# amplifier.net
KiCad netlist of a schematic drawn in EAGLE
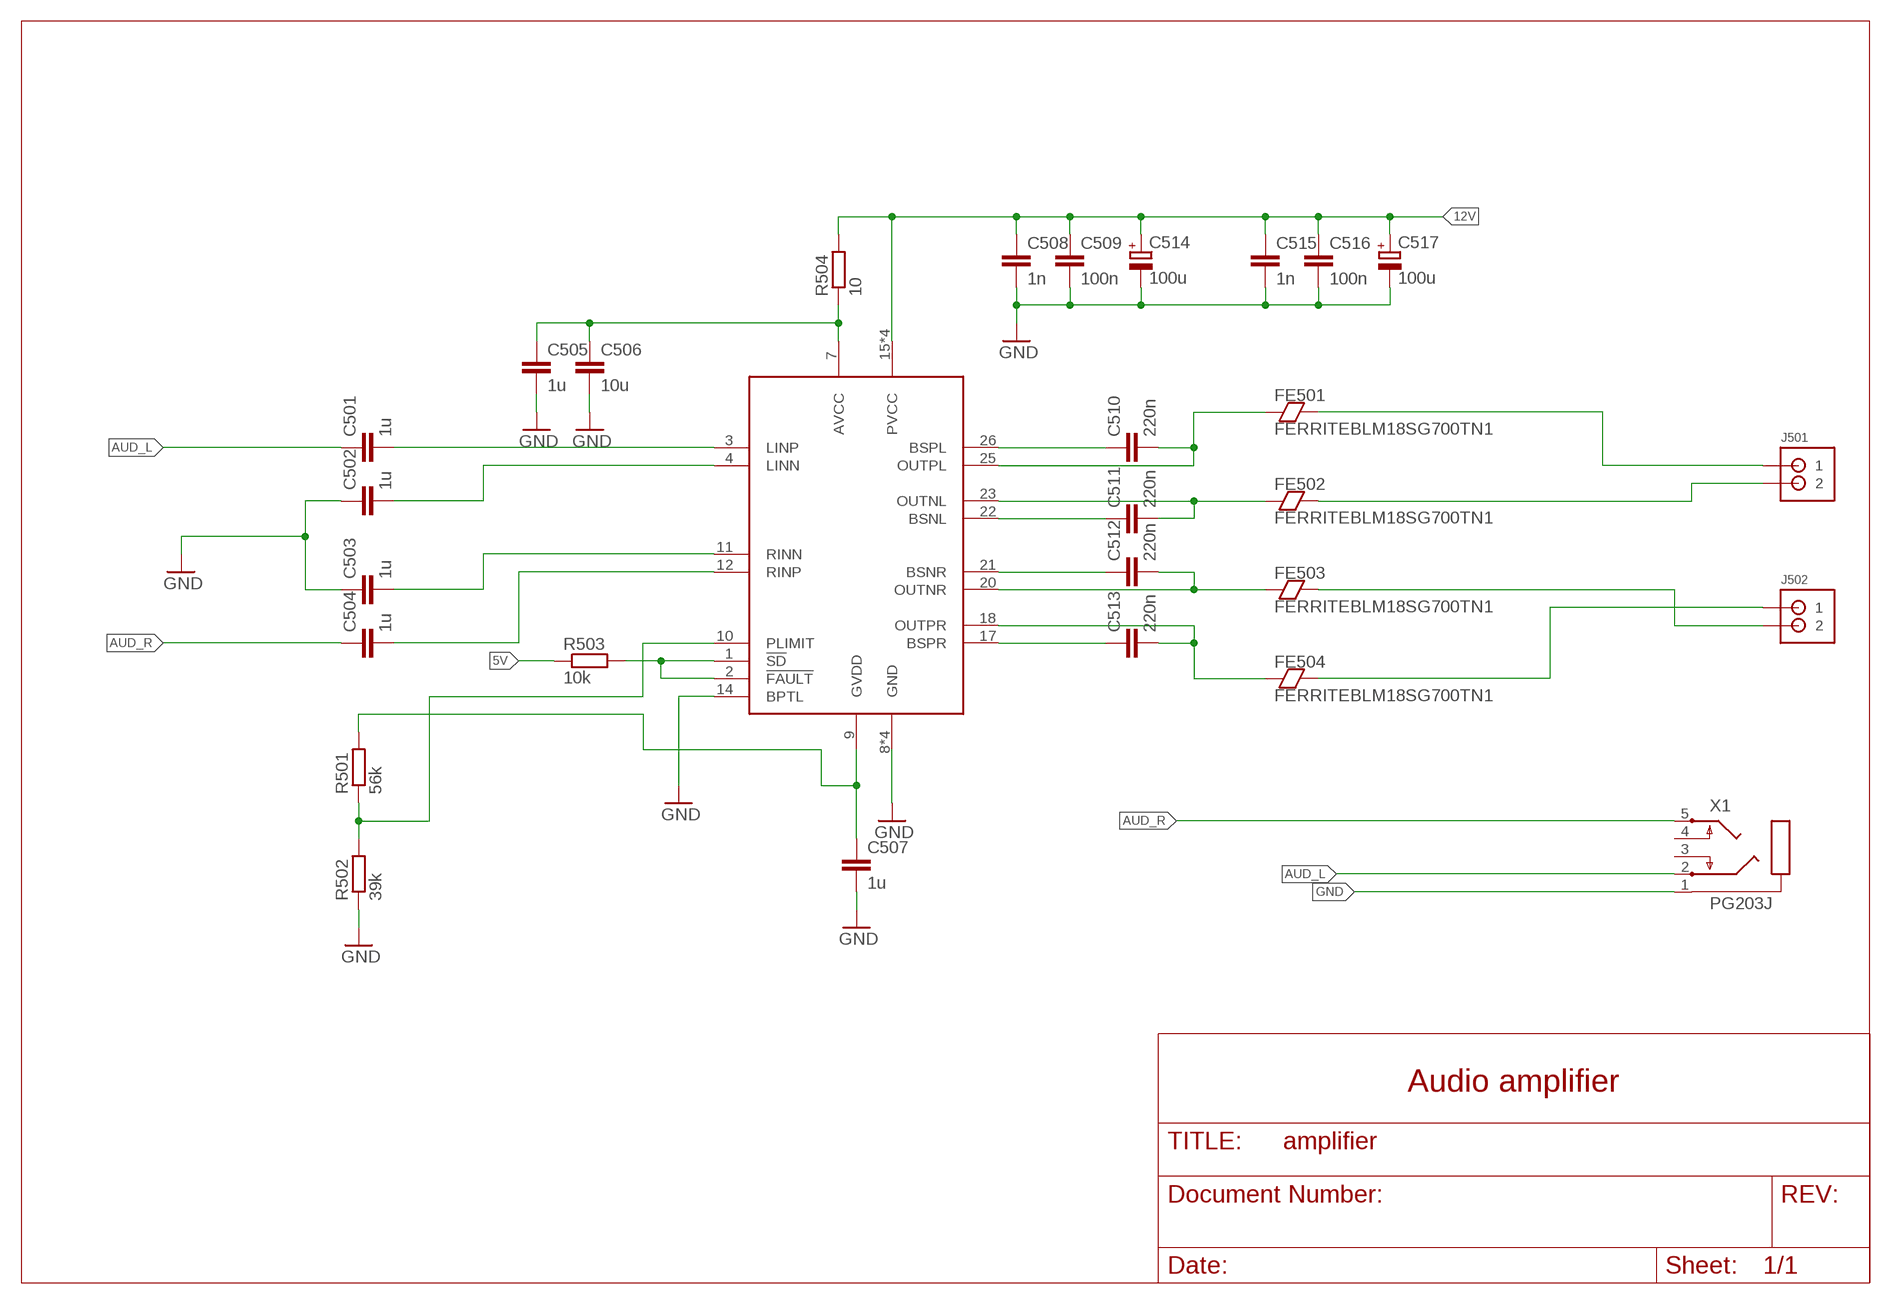
[diagram p0: schematic, sheet 1]

(export (version "E")
  (design (tool "Eeschema 10.0.6"))
  (components
    (comp (ref "C501")
      (value "1u")
      (footprint "eagle-import:C0603")
      (libsource (lib "eagle-import") (part "C0603"))
    )
    (comp (ref "C502")
      (value "1u")
      (footprint "eagle-import:C0603")
      (libsource (lib "eagle-import") (part "C0603"))
    )
    (comp (ref "C503")
      (value "1u")
      (footprint "eagle-import:C0603")
      (libsource (lib "eagle-import") (part "C0603"))
    )
    (comp (ref "C504")
      (value "1u")
      (footprint "eagle-import:C0603")
      (libsource (lib "eagle-import") (part "C0603"))
    )
    (comp (ref "C505")
      (value "1u")
      (footprint "eagle-import:C0603")
      (libsource (lib "eagle-import") (part "C0603"))
    )
    (comp (ref "C506")
      (value "10u")
      (footprint "eagle-import:C0603")
      (libsource (lib "eagle-import") (part "C0603"))
    )
    (comp (ref "C507")
      (value "1u")
      (footprint "eagle-import:C0603")
      (libsource (lib "eagle-import") (part "C0603"))
    )
    (comp (ref "C508")
      (value "1n")
      (footprint "eagle-import:C0603")
      (libsource (lib "eagle-import") (part "C0603"))
    )
    (comp (ref "C509")
      (value "100n")
      (footprint "eagle-import:C0603")
      (libsource (lib "eagle-import") (part "C0603"))
    )
    (comp (ref "C510")
      (value "220n")
      (footprint "eagle-import:C0603")
      (libsource (lib "eagle-import") (part "C0603"))
    )
    (comp (ref "C511")
      (value "220n")
      (footprint "eagle-import:C0603")
      (libsource (lib "eagle-import") (part "C0603"))
    )
    (comp (ref "C512")
      (value "220n")
      (footprint "eagle-import:C0603")
      (libsource (lib "eagle-import") (part "C0603"))
    )
    (comp (ref "C513")
      (value "220n")
      (footprint "eagle-import:C0603")
      (libsource (lib "eagle-import") (part "C0603"))
    )
    (comp (ref "C514")
      (value "100u")
      (footprint "eagle-import:CAP6.6X8")
      (libsource (lib "eagle-import") (part "C_POL6.6"))
    )
    (comp (ref "C515")
      (value "1n")
      (footprint "eagle-import:C0603")
      (libsource (lib "eagle-import") (part "C0603"))
    )
    (comp (ref "C516")
      (value "100n")
      (footprint "eagle-import:C0603")
      (libsource (lib "eagle-import") (part "C0603"))
    )
    (comp (ref "C517")
      (value "100u")
      (footprint "eagle-import:CAP6.6X8")
      (libsource (lib "eagle-import") (part "C_POL6.6"))
    )
    (comp (ref "FE501")
      (value "FERRITEBLM18SG700TN1")
      (footprint "eagle-import:R0603")
      (fields (field (name "MPN") "BLM18SG700TN1D"))
      (libsource (lib "eagle-import") (part "FERRITEBLM18SG700TN1"))
    )
    (comp (ref "FE502")
      (value "FERRITEBLM18SG700TN1")
      (footprint "eagle-import:R0603")
      (fields (field (name "MPN") "BLM18SG700TN1D"))
      (libsource (lib "eagle-import") (part "FERRITEBLM18SG700TN1"))
    )
    (comp (ref "FE503")
      (value "FERRITEBLM18SG700TN1")
      (footprint "eagle-import:R0603")
      (fields (field (name "MPN") "BLM18SG700TN1D"))
      (libsource (lib "eagle-import") (part "FERRITEBLM18SG700TN1"))
    )
    (comp (ref "FE504")
      (value "FERRITEBLM18SG700TN1")
      (footprint "eagle-import:R0603")
      (fields (field (name "MPN") "BLM18SG700TN1D"))
      (libsource (lib "eagle-import") (part "FERRITEBLM18SG700TN1"))
    )
    (comp (ref "J501")
      (value "CONNECTOR-2JST-XH-2")
      (footprint "eagle-import:JST-XH-2")
      (fields (field (name "MPN") "B2B-XH-A (LF)(SN)"))
      (libsource (lib "eagle-import") (part "CONNECTOR-2JST-XH-2"))
    )
    (comp (ref "J502")
      (value "CONNECTOR-2JST-XH-2")
      (footprint "eagle-import:JST-XH-2")
      (fields (field (name "MPN") "B2B-XH-A (LF)(SN)"))
      (libsource (lib "eagle-import") (part "CONNECTOR-2JST-XH-2"))
    )
    (comp (ref "R501")
      (value "56k")
      (footprint "eagle-import:R0603")
      (libsource (lib "eagle-import") (part "R0603"))
    )
    (comp (ref "R502")
      (value "39k")
      (footprint "eagle-import:R0603")
      (libsource (lib "eagle-import") (part "R0603"))
    )
    (comp (ref "R503")
      (value "10k")
      (footprint "eagle-import:R0603")
      (libsource (lib "eagle-import") (part "R0603"))
    )
    (comp (ref "R504")
      (value "10")
      (footprint "eagle-import:R0603")
      (libsource (lib "eagle-import") (part "R0603"))
    )
    (comp (ref "U501")
      (value "TPA3136D2")
      (footprint "eagle-import:R-PDSO-G28")
      (libsource (lib "eagle-import") (part "TPA3136D2"))
    )
    (comp (ref "X1")
      (value "PG203J")
      (footprint "eagle-import:PG203J")
      (libsource (lib "eagle-import") (part "PG203J"))
    )
  )
  (nets
    (net (code "1") (name "5V") (class "Default")
      (node (ref "R503") (pin "1") (pinfunction "1_1") (pintype "passive"))
    )
    (net (code "2") (name "12V") (class "Default")
      (node (ref "C508") (pin "1") (pinfunction "1_1") (pintype "passive"))
      (node (ref "C509") (pin "1") (pinfunction "1_1") (pintype "passive"))
      (node (ref "C514") (pin "1") (pinfunction "+_1") (pintype "passive"))
      (node (ref "C515") (pin "1") (pinfunction "1_1") (pintype "passive"))
      (node (ref "C516") (pin "1") (pinfunction "1_1") (pintype "passive"))
      (node (ref "C517") (pin "1") (pinfunction "+_1") (pintype "passive"))
      (node (ref "R504") (pin "2") (pinfunction "2_2") (pintype "passive"))
      (node (ref "U501") (pin "15") (pinfunction "PVCC_15") (pintype "power_in"))
      (node (ref "U501") (pin "16") (pinfunction "PVCC_16") (pintype "power_in"))
      (node (ref "U501") (pin "27") (pinfunction "PVCC_27") (pintype "power_in"))
      (node (ref "U501") (pin "28") (pinfunction "PVCC_28") (pintype "power_in"))
    )
    (net (code "3") (name "AUD_L") (class "Default")
      (node (ref "C501") (pin "1") (pinfunction "1_1") (pintype "passive"))
      (node (ref "X1") (pin "2") (pinfunction "2_2") (pintype "passive"))
    )
    (net (code "4") (name "AUD_R") (class "Default")
      (node (ref "C504") (pin "1") (pinfunction "1_1") (pintype "passive"))
      (node (ref "X1") (pin "5") (pinfunction "5_5") (pintype "passive"))
    )
    (net (code "5") (name "GND") (class "Default")
      (node (ref "C502") (pin "1") (pinfunction "1_1") (pintype "passive"))
      (node (ref "C503") (pin "1") (pinfunction "1_1") (pintype "passive"))
      (node (ref "C505") (pin "2") (pinfunction "2_2") (pintype "passive"))
      (node (ref "C506") (pin "2") (pinfunction "2_2") (pintype "passive"))
      (node (ref "C507") (pin "2") (pinfunction "2_2") (pintype "passive"))
      (node (ref "C508") (pin "2") (pinfunction "2_2") (pintype "passive"))
      (node (ref "C509") (pin "2") (pinfunction "2_2") (pintype "passive"))
      (node (ref "C514") (pin "2") (pinfunction "-_2") (pintype "passive"))
      (node (ref "C515") (pin "2") (pinfunction "2_2") (pintype "passive"))
      (node (ref "C516") (pin "2") (pinfunction "2_2") (pintype "passive"))
      (node (ref "C517") (pin "2") (pinfunction "-_2") (pintype "passive"))
      (node (ref "R502") (pin "1") (pinfunction "1_1") (pintype "passive"))
      (node (ref "U501") (pin "14") (pinfunction "BPTL_14") (pintype "input"))
      (node (ref "U501") (pin "19") (pinfunction "GND_19") (pintype "power_in"))
      (node (ref "U501") (pin "24") (pinfunction "GND_24") (pintype "power_in"))
      (node (ref "U501") (pin "8") (pinfunction "GND_8") (pintype "power_in"))
      (node (ref "U501") (pin "POWER") (pinfunction "GND_POWER") (pintype "power_in"))
      (node (ref "X1") (pin "1") (pinfunction "1_1") (pintype "passive"))
    )
    (net (code "6") (name "Net-(J501-1)") (class "Default")
      (node (ref "FE501") (pin "2") (pinfunction "2_2") (pintype "passive"))
      (node (ref "J501") (pin "P1") (pinfunction "1_P1") (pintype "bidirectional"))
    )
    (net (code "7") (name "Net-(J501-2)") (class "Default")
      (node (ref "FE502") (pin "2") (pinfunction "2_2") (pintype "passive"))
      (node (ref "J501") (pin "P2") (pinfunction "2_P2") (pintype "bidirectional"))
    )
    (net (code "8") (name "Net-(J502-1)") (class "Default")
      (node (ref "FE504") (pin "2") (pinfunction "2_2") (pintype "passive"))
      (node (ref "J502") (pin "P1") (pinfunction "1_P1") (pintype "bidirectional"))
    )
    (net (code "9") (name "Net-(J502-2)") (class "Default")
      (node (ref "FE503") (pin "2") (pinfunction "2_2") (pintype "passive"))
      (node (ref "J502") (pin "P2") (pinfunction "2_P2") (pintype "bidirectional"))
    )
    (net (code "10") (name "Net-(U501-AVCC)") (class "Default")
      (node (ref "C505") (pin "1") (pinfunction "1_1") (pintype "passive"))
      (node (ref "C506") (pin "1") (pinfunction "1_1") (pintype "passive"))
      (node (ref "R504") (pin "1") (pinfunction "1_1") (pintype "passive"))
      (node (ref "U501") (pin "7") (pinfunction "AVCC_7") (pintype "power_in"))
    )
    (net (code "11") (name "Net-(U501-BSNL)") (class "Default")
      (node (ref "C511") (pin "1") (pinfunction "1_1") (pintype "passive"))
      (node (ref "U501") (pin "22") (pinfunction "BSNL_22") (pintype "input"))
    )
    (net (code "12") (name "Net-(U501-BSNR)") (class "Default")
      (node (ref "C512") (pin "1") (pinfunction "1_1") (pintype "passive"))
      (node (ref "U501") (pin "21") (pinfunction "BSNR_21") (pintype "input"))
    )
    (net (code "13") (name "Net-(U501-BSPL)") (class "Default")
      (node (ref "C510") (pin "1") (pinfunction "1_1") (pintype "passive"))
      (node (ref "U501") (pin "26") (pinfunction "BSPL_26") (pintype "input"))
    )
    (net (code "14") (name "Net-(U501-BSPR)") (class "Default")
      (node (ref "C513") (pin "1") (pinfunction "1_1") (pintype "passive"))
      (node (ref "U501") (pin "17") (pinfunction "BSPR_17") (pintype "input"))
    )
    (net (code "15") (name "Net-(U501-GVDD)") (class "Default")
      (node (ref "C507") (pin "1") (pinfunction "1_1") (pintype "passive"))
      (node (ref "R501") (pin "2") (pinfunction "2_2") (pintype "passive"))
      (node (ref "U501") (pin "9") (pinfunction "GVDD_9") (pintype "power_in"))
    )
    (net (code "16") (name "Net-(U501-LINN)") (class "Default")
      (node (ref "C502") (pin "2") (pinfunction "2_2") (pintype "passive"))
      (node (ref "U501") (pin "4") (pinfunction "LINN_4") (pintype "input"))
    )
    (net (code "17") (name "Net-(U501-LINP)") (class "Default")
      (node (ref "C501") (pin "2") (pinfunction "2_2") (pintype "passive"))
      (node (ref "U501") (pin "3") (pinfunction "LINP_3") (pintype "input"))
    )
    (net (code "18") (name "Net-(U501-OUTNL)") (class "Default")
      (node (ref "C511") (pin "2") (pinfunction "2_2") (pintype "passive"))
      (node (ref "FE502") (pin "1") (pinfunction "1_1") (pintype "passive"))
      (node (ref "U501") (pin "23") (pinfunction "OUTNL_23") (pintype "output"))
    )
    (net (code "19") (name "Net-(U501-OUTNR)") (class "Default")
      (node (ref "C512") (pin "2") (pinfunction "2_2") (pintype "passive"))
      (node (ref "FE503") (pin "1") (pinfunction "1_1") (pintype "passive"))
      (node (ref "U501") (pin "20") (pinfunction "OUTNR_20") (pintype "output"))
    )
    (net (code "20") (name "Net-(U501-OUTPL)") (class "Default")
      (node (ref "C510") (pin "2") (pinfunction "2_2") (pintype "passive"))
      (node (ref "FE501") (pin "1") (pinfunction "1_1") (pintype "passive"))
      (node (ref "U501") (pin "25") (pinfunction "OUTPL_25") (pintype "output"))
    )
    (net (code "21") (name "Net-(U501-OUTPR)") (class "Default")
      (node (ref "C513") (pin "2") (pinfunction "2_2") (pintype "passive"))
      (node (ref "FE504") (pin "1") (pinfunction "1_1") (pintype "passive"))
      (node (ref "U501") (pin "18") (pinfunction "OUTPR_18") (pintype "output"))
    )
    (net (code "22") (name "Net-(U501-PLIMIT)") (class "Default")
      (node (ref "R501") (pin "1") (pinfunction "1_1") (pintype "passive"))
      (node (ref "R502") (pin "2") (pinfunction "2_2") (pintype "passive"))
      (node (ref "U501") (pin "10") (pinfunction "PLIMIT_10") (pintype "bidirectional"))
    )
    (net (code "23") (name "Net-(U501-RINN)") (class "Default")
      (node (ref "C503") (pin "2") (pinfunction "2_2") (pintype "passive"))
      (node (ref "U501") (pin "11") (pinfunction "RINN_11") (pintype "input"))
    )
    (net (code "24") (name "Net-(U501-RINP)") (class "Default")
      (node (ref "C504") (pin "2") (pinfunction "2_2") (pintype "passive"))
      (node (ref "U501") (pin "12") (pinfunction "RINP_12") (pintype "input"))
    )
    (net (code "25") (name "Net-(U501-~{FAULT})") (class "Default")
      (node (ref "R503") (pin "2") (pinfunction "2_2") (pintype "passive"))
      (node (ref "U501") (pin "1") (pinfunction "~{SD}_1") (pintype "input"))
      (node (ref "U501") (pin "2") (pinfunction "~{FAULT}_2") (pintype "output"))
    )
    (net (code "26") (name "unconnected-(X1-Pad3)") (class "Default")
      (node (ref "X1") (pin "3") (pinfunction "3_3") (pintype "passive"))
    )
    (net (code "27") (name "unconnected-(X1-Pad4)") (class "Default")
      (node (ref "X1") (pin "4") (pinfunction "4_4") (pintype "passive"))
    )
  )
)
